# M1703C.net
KiCad netlist of a schematic drawn in EAGLE
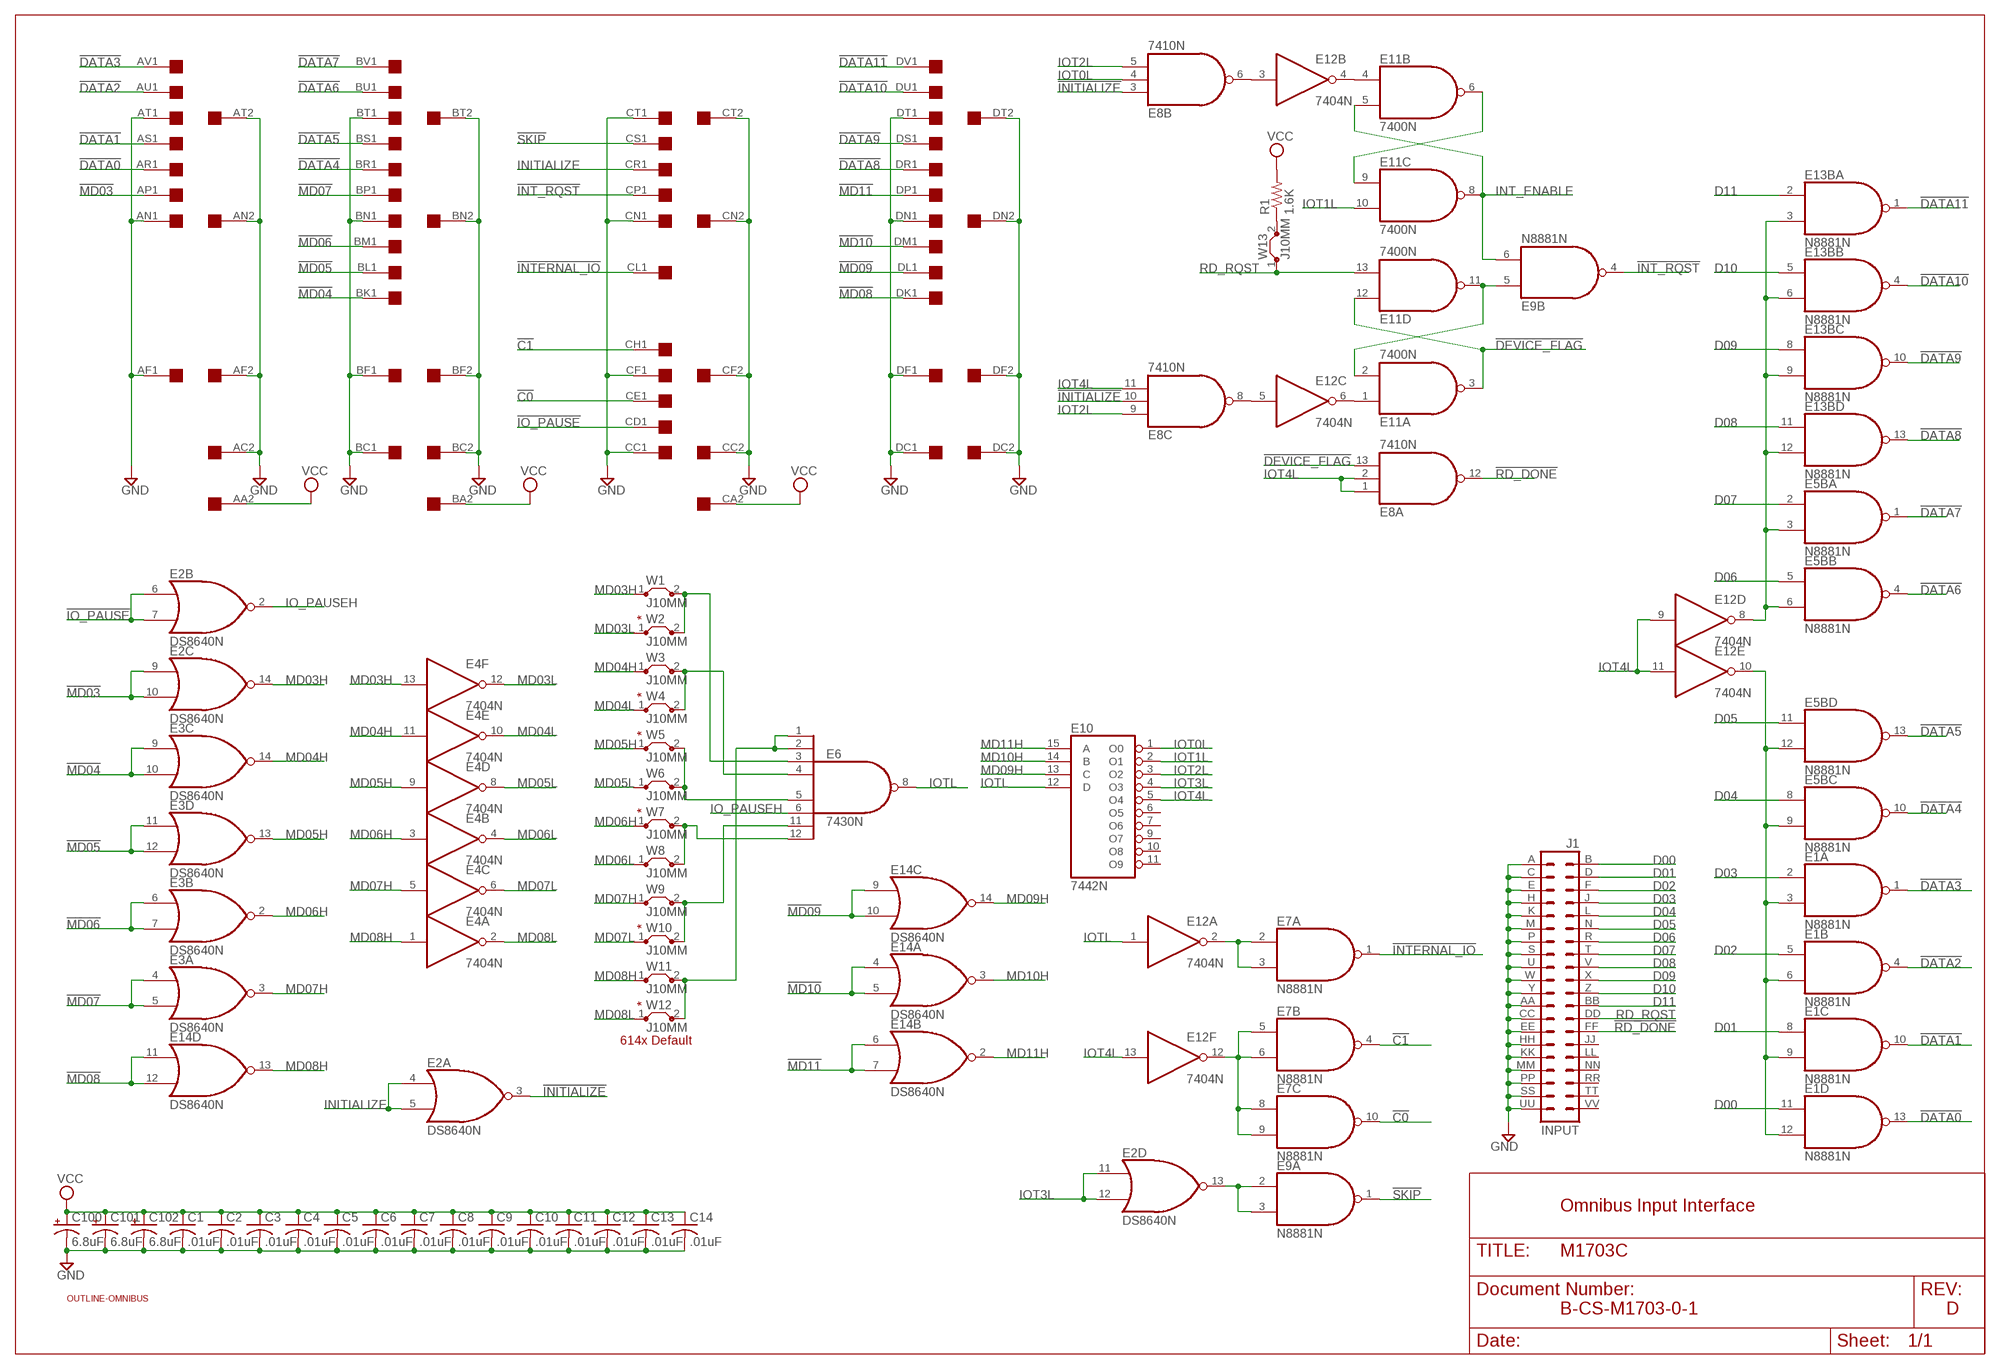
[diagram p0: schematic, sheet 1]

(export (version "E")
  (design (tool "Eeschema 10.0.6"))
  (components
    (comp (ref "C1")
      (value ".01uF")
      (footprint "eagle-import:C075-032X103")
      (libsource (lib "eagle-import") (part "C-US075-032X103"))
    )
    (comp (ref "C2")
      (value ".01uF")
      (footprint "eagle-import:C075-032X103")
      (libsource (lib "eagle-import") (part "C-US075-032X103"))
    )
    (comp (ref "C3")
      (value ".01uF")
      (footprint "eagle-import:C075-032X103")
      (libsource (lib "eagle-import") (part "C-US075-032X103"))
    )
    (comp (ref "C4")
      (value ".01uF")
      (footprint "eagle-import:C075-032X103")
      (libsource (lib "eagle-import") (part "C-US075-032X103"))
    )
    (comp (ref "C5")
      (value ".01uF")
      (footprint "eagle-import:C075-032X103")
      (libsource (lib "eagle-import") (part "C-US075-032X103"))
    )
    (comp (ref "C6")
      (value ".01uF")
      (footprint "eagle-import:C075-032X103")
      (libsource (lib "eagle-import") (part "C-US075-032X103"))
    )
    (comp (ref "C7")
      (value ".01uF")
      (footprint "eagle-import:C075-032X103")
      (libsource (lib "eagle-import") (part "C-US075-032X103"))
    )
    (comp (ref "C8")
      (value ".01uF")
      (footprint "eagle-import:C075-032X103")
      (libsource (lib "eagle-import") (part "C-US075-032X103"))
    )
    (comp (ref "C9")
      (value ".01uF")
      (footprint "eagle-import:C075-032X103")
      (libsource (lib "eagle-import") (part "C-US075-032X103"))
    )
    (comp (ref "C10")
      (value ".01uF")
      (footprint "eagle-import:C075-032X103")
      (libsource (lib "eagle-import") (part "C-US075-032X103"))
    )
    (comp (ref "C11")
      (value ".01uF")
      (footprint "eagle-import:C075-032X103")
      (libsource (lib "eagle-import") (part "C-US075-032X103"))
    )
    (comp (ref "C12")
      (value ".01uF")
      (footprint "eagle-import:C075-032X103")
      (libsource (lib "eagle-import") (part "C-US075-032X103"))
    )
    (comp (ref "C13")
      (value ".01uF")
      (footprint "eagle-import:C075-032X103")
      (libsource (lib "eagle-import") (part "C-US075-032X103"))
    )
    (comp (ref "C14")
      (value ".01uF")
      (footprint "eagle-import:C075-032X103")
      (libsource (lib "eagle-import") (part "C-US075-032X103"))
    )
    (comp (ref "C100")
      (value "6.8uF")
      (footprint "eagle-import:E12-8")
      (libsource (lib "eagle-import") (part "CPOL-USE20-8AXIAL"))
    )
    (comp (ref "C101")
      (value "6.8uF")
      (footprint "eagle-import:E12-8")
      (libsource (lib "eagle-import") (part "CPOL-USE20-8AXIAL"))
    )
    (comp (ref "C102")
      (value "6.8uF")
      (footprint "eagle-import:E12-8")
      (libsource (lib "eagle-import") (part "CPOL-USE20-8AXIAL"))
    )
    (comp (ref "E1")
      (value "N8881N")
      (footprint "eagle-import:DIL14")
      (libsource (lib "eagle-import") (part "N8881N"))
    )
    (comp (ref "E2")
      (value "DS8640N")
      (footprint "eagle-import:DIL14")
      (libsource (lib "eagle-import") (part "DS8640N"))
    )
    (comp (ref "E3")
      (value "DS8640N")
      (footprint "eagle-import:DIL14")
      (libsource (lib "eagle-import") (part "DS8640N"))
    )
    (comp (ref "E4")
      (value "7404N")
      (footprint "eagle-import:DIL14")
      (libsource (lib "eagle-import") (part "7404N"))
    )
    (comp (ref "E5B")
      (value "N8881N")
      (footprint "eagle-import:DIL14")
      (libsource (lib "eagle-import") (part "N8881N"))
    )
    (comp (ref "E6")
      (value "7430N")
      (footprint "eagle-import:DIL14")
      (libsource (lib "eagle-import") (part "7430N"))
    )
    (comp (ref "E7")
      (value "N8881N")
      (footprint "eagle-import:DIL14")
      (libsource (lib "eagle-import") (part "N8881N"))
    )
    (comp (ref "E8")
      (value "7410N")
      (footprint "eagle-import:DIL14")
      (libsource (lib "eagle-import") (part "7410N"))
    )
    (comp (ref "E9")
      (value "N8881N")
      (footprint "eagle-import:DIL14")
      (libsource (lib "eagle-import") (part "N8881N"))
    )
    (comp (ref "E10")
      (value "7442N")
      (footprint "eagle-import:DIL16")
      (libsource (lib "eagle-import") (part "7442NLS"))
    )
    (comp (ref "E11")
      (value "7400N")
      (footprint "eagle-import:DIL14")
      (libsource (lib "eagle-import") (part "7400N"))
    )
    (comp (ref "E12")
      (value "7404N")
      (footprint "eagle-import:DIL14")
      (libsource (lib "eagle-import") (part "7404N"))
    )
    (comp (ref "E13B")
      (value "N8881N")
      (footprint "eagle-import:DIL14")
      (libsource (lib "eagle-import") (part "N8881N"))
    )
    (comp (ref "E14")
      (value "DS8640N")
      (footprint "eagle-import:DIL14")
      (libsource (lib "eagle-import") (part "DS8640N"))
    )
    (comp (ref "J1")
      (value "INPUT")
      (footprint "eagle-import:DEC40PINH")
      (libsource (lib "eagle-import") (part "DEC40PINH"))
    )
    (comp (ref "R1")
      (value "1.6K")
      (footprint "eagle-import:0207_10")
      (libsource (lib "eagle-import") (part "R-US_0207/10"))
    )
    (comp (ref "U$2")
      (value "QUAD")
      (footprint "eagle-import:EDGE-CON8")
      (libsource (lib "eagle-import") (part "QUAD"))
    )
    (comp (ref "U$4")
      (value "OUTLINE-OMNIBUS")
      (footprint "eagle-import:OMNIBUS")
      (libsource (lib "eagle-import") (part "OUTLINE-OMNIBUS"))
    )
    (comp (ref "W1")
      (value "J10MM")
      (footprint "eagle-import:10")
      (libsource (lib "eagle-import") (part "J10MM"))
    )
    (comp (ref "W2")
      (value "J10MM")
      (footprint "eagle-import:10")
      (libsource (lib "eagle-import") (part "J10MM"))
    )
    (comp (ref "W3")
      (value "J10MM")
      (footprint "eagle-import:10")
      (libsource (lib "eagle-import") (part "J10MM"))
    )
    (comp (ref "W4")
      (value "J10MM")
      (footprint "eagle-import:10")
      (libsource (lib "eagle-import") (part "J10MM"))
    )
    (comp (ref "W5")
      (value "J10MM")
      (footprint "eagle-import:10")
      (libsource (lib "eagle-import") (part "J10MM"))
    )
    (comp (ref "W6")
      (value "J10MM")
      (footprint "eagle-import:10")
      (libsource (lib "eagle-import") (part "J10MM"))
    )
    (comp (ref "W7")
      (value "J10MM")
      (footprint "eagle-import:10")
      (libsource (lib "eagle-import") (part "J10MM"))
    )
    (comp (ref "W8")
      (value "J10MM")
      (footprint "eagle-import:10")
      (libsource (lib "eagle-import") (part "J10MM"))
    )
    (comp (ref "W9")
      (value "J10MM")
      (footprint "eagle-import:10")
      (libsource (lib "eagle-import") (part "J10MM"))
    )
    (comp (ref "W10")
      (value "J10MM")
      (footprint "eagle-import:10")
      (libsource (lib "eagle-import") (part "J10MM"))
    )
    (comp (ref "W11")
      (value "J10MM")
      (footprint "eagle-import:10")
      (libsource (lib "eagle-import") (part "J10MM"))
    )
    (comp (ref "W12")
      (value "J10MM")
      (footprint "eagle-import:10")
      (libsource (lib "eagle-import") (part "J10MM"))
    )
    (comp (ref "W13")
      (value "J10MM")
      (footprint "eagle-import:10")
      (libsource (lib "eagle-import") (part "J10MM"))
    )
  )
  (nets
    (net (code "1") (name "/D00") (class "Default")
      (node (ref "E1") (pin "11") (pinfunction "I0_11") (pintype "input"))
      (node (ref "J1") (pin "B") (pinfunction "2_B") (pintype "bidirectional"))
    )
    (net (code "2") (name "/D01") (class "Default")
      (node (ref "E1") (pin "8") (pinfunction "I0_8") (pintype "input"))
      (node (ref "J1") (pin "D") (pinfunction "4_D") (pintype "bidirectional"))
    )
    (net (code "3") (name "/D02") (class "Default")
      (node (ref "E1") (pin "5") (pinfunction "I0_5") (pintype "input"))
      (node (ref "J1") (pin "F") (pinfunction "6_F") (pintype "bidirectional"))
    )
    (net (code "4") (name "/D03") (class "Default")
      (node (ref "E1") (pin "2") (pinfunction "I0_2") (pintype "input"))
      (node (ref "J1") (pin "J") (pinfunction "8_J") (pintype "bidirectional"))
    )
    (net (code "5") (name "/D04") (class "Default")
      (node (ref "E5B") (pin "8") (pinfunction "I0_8") (pintype "input"))
      (node (ref "J1") (pin "L") (pinfunction "10_L") (pintype "bidirectional"))
    )
    (net (code "6") (name "/D05") (class "Default")
      (node (ref "E5B") (pin "11") (pinfunction "I0_11") (pintype "input"))
      (node (ref "J1") (pin "N") (pinfunction "12_N") (pintype "bidirectional"))
    )
    (net (code "7") (name "/D06") (class "Default")
      (node (ref "E5B") (pin "5") (pinfunction "I0_5") (pintype "input"))
      (node (ref "J1") (pin "R") (pinfunction "14_R") (pintype "bidirectional"))
    )
    (net (code "8") (name "/D07") (class "Default")
      (node (ref "E5B") (pin "2") (pinfunction "I0_2") (pintype "input"))
      (node (ref "J1") (pin "T") (pinfunction "16_T") (pintype "bidirectional"))
    )
    (net (code "9") (name "/D08") (class "Default")
      (node (ref "E13B") (pin "11") (pinfunction "I0_11") (pintype "input"))
      (node (ref "J1") (pin "V") (pinfunction "18_V") (pintype "bidirectional"))
    )
    (net (code "10") (name "/D09") (class "Default")
      (node (ref "E13B") (pin "8") (pinfunction "I0_8") (pintype "input"))
      (node (ref "J1") (pin "X") (pinfunction "20_X") (pintype "bidirectional"))
    )
    (net (code "11") (name "/D10") (class "Default")
      (node (ref "E13B") (pin "5") (pinfunction "I0_5") (pintype "input"))
      (node (ref "J1") (pin "Z") (pinfunction "22_Z") (pintype "bidirectional"))
    )
    (net (code "12") (name "/D11") (class "Default")
      (node (ref "E13B") (pin "2") (pinfunction "I0_2") (pintype "input"))
      (node (ref "J1") (pin "BB") (pinfunction "24_BB") (pintype "bidirectional"))
    )
    (net (code "13") (name "/INITIALIZE") (class "Default")
      (node (ref "E2") (pin "4") (pinfunction "I0_4") (pintype "input"))
      (node (ref "E2") (pin "5") (pinfunction "I1_5") (pintype "input"))
      (node (ref "U$2") (pin "CR1") (pinfunction "1_CR1") (pintype "bidirectional"))
    )
    (net (code "14") (name "/INT_ENABLE") (class "Default")
      (node (ref "E11") (pin "5") (pinfunction "I1_5") (pintype "input"))
      (node (ref "E11") (pin "8") (pinfunction "O_8") (pintype "output"))
      (node (ref "E9") (pin "6") (pinfunction "I1_6") (pintype "input"))
    )
    (net (code "15") (name "/IOT0L") (class "Default")
      (node (ref "E10") (pin "1") (pinfunction "O0_1") (pintype "output"))
      (node (ref "E8") (pin "4") (pinfunction "I1_4") (pintype "input"))
    )
    (net (code "16") (name "/IOT1L") (class "Default")
      (node (ref "E10") (pin "2") (pinfunction "O1_2") (pintype "output"))
      (node (ref "E11") (pin "10") (pinfunction "I1_10") (pintype "input"))
    )
    (net (code "17") (name "/IOT2L") (class "Default")
      (node (ref "E10") (pin "3") (pinfunction "O2_3") (pintype "output"))
      (node (ref "E8") (pin "5") (pinfunction "I2_5") (pintype "input"))
      (node (ref "E8") (pin "9") (pinfunction "I0_9") (pintype "input"))
    )
    (net (code "18") (name "/IOT3L") (class "Default")
      (node (ref "E10") (pin "4") (pinfunction "O3_4") (pintype "output"))
      (node (ref "E2") (pin "11") (pinfunction "I0_11") (pintype "input"))
      (node (ref "E2") (pin "12") (pinfunction "I1_12") (pintype "input"))
    )
    (net (code "19") (name "/IOT4L") (class "Default")
      (node (ref "E10") (pin "5") (pinfunction "O4_5") (pintype "output"))
      (node (ref "E12") (pin "11") (pinfunction "I_11") (pintype "input"))
      (node (ref "E12") (pin "13") (pinfunction "I_13") (pintype "input"))
      (node (ref "E12") (pin "9") (pinfunction "I_9") (pintype "input"))
      (node (ref "E8") (pin "1") (pinfunction "I0_1") (pintype "input"))
      (node (ref "E8") (pin "11") (pinfunction "I2_11") (pintype "input"))
      (node (ref "E8") (pin "2") (pinfunction "I1_2") (pintype "input"))
    )
    (net (code "20") (name "/IOTL") (class "Default")
      (node (ref "E10") (pin "12") (pinfunction "D_12") (pintype "input"))
      (node (ref "E12") (pin "1") (pinfunction "I_1") (pintype "input"))
      (node (ref "E6") (pin "8") (pinfunction "O_8") (pintype "output"))
    )
    (net (code "21") (name "/IO_PAUSEH") (class "Default")
      (node (ref "E2") (pin "2") (pinfunction "O_2") (pintype "output"))
      (node (ref "E6") (pin "6") (pinfunction "I5_6") (pintype "input"))
    )
    (net (code "22") (name "/MD03H") (class "Default")
      (node (ref "E2") (pin "14") (pinfunction "O_14") (pintype "output"))
      (node (ref "E4") (pin "13") (pinfunction "I_13") (pintype "input"))
      (node (ref "W1") (pin "1") (pinfunction "1_1") (pintype "passive"))
    )
    (net (code "23") (name "/MD03L") (class "Default")
      (node (ref "E4") (pin "12") (pinfunction "O_12") (pintype "output"))
      (node (ref "W2") (pin "1") (pinfunction "1_1") (pintype "passive"))
    )
    (net (code "24") (name "/MD04H") (class "Default")
      (node (ref "E3") (pin "14") (pinfunction "O_14") (pintype "output"))
      (node (ref "E4") (pin "11") (pinfunction "I_11") (pintype "input"))
      (node (ref "W3") (pin "1") (pinfunction "1_1") (pintype "passive"))
    )
    (net (code "25") (name "/MD04L") (class "Default")
      (node (ref "E4") (pin "10") (pinfunction "O_10") (pintype "output"))
      (node (ref "W4") (pin "1") (pinfunction "1_1") (pintype "passive"))
    )
    (net (code "26") (name "/MD05H") (class "Default")
      (node (ref "E3") (pin "13") (pinfunction "O_13") (pintype "output"))
      (node (ref "E4") (pin "9") (pinfunction "I_9") (pintype "input"))
      (node (ref "W5") (pin "1") (pinfunction "1_1") (pintype "passive"))
    )
    (net (code "27") (name "/MD05L") (class "Default")
      (node (ref "E4") (pin "8") (pinfunction "O_8") (pintype "output"))
      (node (ref "W6") (pin "1") (pinfunction "1_1") (pintype "passive"))
    )
    (net (code "28") (name "/MD06H") (class "Default")
      (node (ref "E3") (pin "2") (pinfunction "O_2") (pintype "output"))
      (node (ref "E4") (pin "3") (pinfunction "I_3") (pintype "input"))
      (node (ref "W7") (pin "1") (pinfunction "1_1") (pintype "passive"))
    )
    (net (code "29") (name "/MD06L") (class "Default")
      (node (ref "E4") (pin "4") (pinfunction "O_4") (pintype "output"))
      (node (ref "W8") (pin "1") (pinfunction "1_1") (pintype "passive"))
    )
    (net (code "30") (name "/MD07H") (class "Default")
      (node (ref "E3") (pin "3") (pinfunction "O_3") (pintype "output"))
      (node (ref "E4") (pin "5") (pinfunction "I_5") (pintype "input"))
      (node (ref "W9") (pin "1") (pinfunction "1_1") (pintype "passive"))
    )
    (net (code "31") (name "/MD07L") (class "Default")
      (node (ref "E4") (pin "6") (pinfunction "O_6") (pintype "output"))
      (node (ref "W10") (pin "1") (pinfunction "1_1") (pintype "passive"))
    )
    (net (code "32") (name "/MD08H") (class "Default")
      (node (ref "E14") (pin "13") (pinfunction "O_13") (pintype "output"))
      (node (ref "E4") (pin "1") (pinfunction "I_1") (pintype "input"))
      (node (ref "W11") (pin "1") (pinfunction "1_1") (pintype "passive"))
    )
    (net (code "33") (name "/MD08L") (class "Default")
      (node (ref "E4") (pin "2") (pinfunction "O_2") (pintype "output"))
      (node (ref "W12") (pin "1") (pinfunction "1_1") (pintype "passive"))
    )
    (net (code "34") (name "/MD09H") (class "Default")
      (node (ref "E10") (pin "13") (pinfunction "C_13") (pintype "input"))
      (node (ref "E14") (pin "14") (pinfunction "O_14") (pintype "output"))
    )
    (net (code "35") (name "/MD10H") (class "Default")
      (node (ref "E10") (pin "14") (pinfunction "B_14") (pintype "input"))
      (node (ref "E14") (pin "3") (pinfunction "O_3") (pintype "output"))
    )
    (net (code "36") (name "/MD11H") (class "Default")
      (node (ref "E10") (pin "15") (pinfunction "A_15") (pintype "input"))
      (node (ref "E14") (pin "2") (pinfunction "O_2") (pintype "output"))
    )
    (net (code "37") (name "/RD_RQST") (class "Default")
      (node (ref "E11") (pin "13") (pinfunction "I1_13") (pintype "input"))
      (node (ref "J1") (pin "DD") (pinfunction "26_DD") (pintype "bidirectional"))
      (node (ref "W13") (pin "1") (pinfunction "1_1") (pintype "passive"))
    )
    (net (code "38") (name "/~{C0}") (class "Default")
      (node (ref "E7") (pin "10") (pinfunction "O_10") (pintype "open_collector"))
      (node (ref "U$2") (pin "CE1") (pinfunction "1_CE1") (pintype "bidirectional"))
    )
    (net (code "39") (name "/~{C1}") (class "Default")
      (node (ref "E7") (pin "4") (pinfunction "O_4") (pintype "open_collector"))
      (node (ref "U$2") (pin "CH1") (pinfunction "1_CH1") (pintype "bidirectional"))
    )
    (net (code "40") (name "/~{DATA0}") (class "Default")
      (node (ref "E1") (pin "13") (pinfunction "O_13") (pintype "open_collector"))
      (node (ref "U$2") (pin "AR1") (pinfunction "1_AR1") (pintype "bidirectional"))
    )
    (net (code "41") (name "/~{DATA1}") (class "Default")
      (node (ref "E1") (pin "10") (pinfunction "O_10") (pintype "open_collector"))
      (node (ref "U$2") (pin "AS1") (pinfunction "1_AS1") (pintype "bidirectional"))
    )
    (net (code "42") (name "/~{DATA2}") (class "Default")
      (node (ref "E1") (pin "4") (pinfunction "O_4") (pintype "open_collector"))
      (node (ref "U$2") (pin "AU1") (pinfunction "1_AU1") (pintype "bidirectional"))
    )
    (net (code "43") (name "/~{DATA3}") (class "Default")
      (node (ref "E1") (pin "1") (pinfunction "O_1") (pintype "open_collector"))
      (node (ref "U$2") (pin "AV1") (pinfunction "1_AV1") (pintype "bidirectional"))
    )
    (net (code "44") (name "/~{DATA4}") (class "Default")
      (node (ref "E5B") (pin "10") (pinfunction "O_10") (pintype "open_collector"))
      (node (ref "U$2") (pin "BR1") (pinfunction "1_BR1") (pintype "bidirectional"))
    )
    (net (code "45") (name "/~{DATA5}") (class "Default")
      (node (ref "E5B") (pin "13") (pinfunction "O_13") (pintype "open_collector"))
      (node (ref "U$2") (pin "BS1") (pinfunction "1_BS1") (pintype "bidirectional"))
    )
    (net (code "46") (name "/~{DATA6}") (class "Default")
      (node (ref "E5B") (pin "4") (pinfunction "O_4") (pintype "open_collector"))
      (node (ref "U$2") (pin "BU1") (pinfunction "1_BU1") (pintype "bidirectional"))
    )
    (net (code "47") (name "/~{DATA7}") (class "Default")
      (node (ref "E5B") (pin "1") (pinfunction "O_1") (pintype "open_collector"))
      (node (ref "U$2") (pin "BV1") (pinfunction "1_BV1") (pintype "bidirectional"))
    )
    (net (code "48") (name "/~{DATA8}") (class "Default")
      (node (ref "E13B") (pin "13") (pinfunction "O_13") (pintype "open_collector"))
      (node (ref "U$2") (pin "DR1") (pinfunction "1_DR1") (pintype "bidirectional"))
    )
    (net (code "49") (name "/~{DATA9}") (class "Default")
      (node (ref "E13B") (pin "10") (pinfunction "O_10") (pintype "open_collector"))
      (node (ref "U$2") (pin "DS1") (pinfunction "1_DS1") (pintype "bidirectional"))
    )
    (net (code "50") (name "/~{DATA10}") (class "Default")
      (node (ref "E13B") (pin "4") (pinfunction "O_4") (pintype "open_collector"))
      (node (ref "U$2") (pin "DU1") (pinfunction "1_DU1") (pintype "bidirectional"))
    )
    (net (code "51") (name "/~{DATA11}") (class "Default")
      (node (ref "E13B") (pin "1") (pinfunction "O_1") (pintype "open_collector"))
      (node (ref "U$2") (pin "DV1") (pinfunction "1_DV1") (pintype "bidirectional"))
    )
    (net (code "52") (name "/~{DEVICE_FLAG}") (class "Default")
      (node (ref "E11") (pin "12") (pinfunction "I0_12") (pintype "input"))
      (node (ref "E11") (pin "3") (pinfunction "O_3") (pintype "output"))
      (node (ref "E8") (pin "13") (pinfunction "I2_13") (pintype "input"))
    )
    (net (code "53") (name "/~{INITIALIZE}") (class "Default")
      (node (ref "E2") (pin "3") (pinfunction "O_3") (pintype "output"))
      (node (ref "E8") (pin "10") (pinfunction "I1_10") (pintype "input"))
      (node (ref "E8") (pin "3") (pinfunction "I0_3") (pintype "input"))
    )
    (net (code "54") (name "/~{INTERNAL_IO}") (class "Default")
      (node (ref "E7") (pin "1") (pinfunction "O_1") (pintype "open_collector"))
      (node (ref "U$2") (pin "CL1") (pinfunction "1_CL1") (pintype "bidirectional"))
    )
    (net (code "55") (name "/~{INT_RQST}") (class "Default")
      (node (ref "E9") (pin "4") (pinfunction "O_4") (pintype "open_collector"))
      (node (ref "U$2") (pin "CP1") (pinfunction "1_CP1") (pintype "bidirectional"))
    )
    (net (code "56") (name "/~{IO_PAUSE}") (class "Default")
      (node (ref "E2") (pin "6") (pinfunction "I0_6") (pintype "input"))
      (node (ref "E2") (pin "7") (pinfunction "I1_7") (pintype "input"))
      (node (ref "U$2") (pin "CD1") (pinfunction "1_CD1") (pintype "bidirectional"))
    )
    (net (code "57") (name "/~{MD03}") (class "Default")
      (node (ref "E2") (pin "10") (pinfunction "I1_10") (pintype "input"))
      (node (ref "E2") (pin "9") (pinfunction "I0_9") (pintype "input"))
      (node (ref "U$2") (pin "AP1") (pinfunction "1_AP1") (pintype "bidirectional"))
    )
    (net (code "58") (name "/~{MD04}") (class "Default")
      (node (ref "E3") (pin "10") (pinfunction "I1_10") (pintype "input"))
      (node (ref "E3") (pin "9") (pinfunction "I0_9") (pintype "input"))
      (node (ref "U$2") (pin "BK1") (pinfunction "1_BK1") (pintype "bidirectional"))
    )
    (net (code "59") (name "/~{MD05}") (class "Default")
      (node (ref "E3") (pin "11") (pinfunction "I0_11") (pintype "input"))
      (node (ref "E3") (pin "12") (pinfunction "I1_12") (pintype "input"))
      (node (ref "U$2") (pin "BL1") (pinfunction "1_BL1") (pintype "bidirectional"))
    )
    (net (code "60") (name "/~{MD06}") (class "Default")
      (node (ref "E3") (pin "6") (pinfunction "I0_6") (pintype "input"))
      (node (ref "E3") (pin "7") (pinfunction "I1_7") (pintype "input"))
      (node (ref "U$2") (pin "BM1") (pinfunction "1_BM1") (pintype "bidirectional"))
    )
    (net (code "61") (name "/~{MD07}") (class "Default")
      (node (ref "E3") (pin "4") (pinfunction "I0_4") (pintype "input"))
      (node (ref "E3") (pin "5") (pinfunction "I1_5") (pintype "input"))
      (node (ref "U$2") (pin "BP1") (pinfunction "1_BP1") (pintype "bidirectional"))
    )
    (net (code "62") (name "/~{MD08}") (class "Default")
      (node (ref "E14") (pin "11") (pinfunction "I0_11") (pintype "input"))
      (node (ref "E14") (pin "12") (pinfunction "I1_12") (pintype "input"))
      (node (ref "U$2") (pin "DK1") (pinfunction "1_DK1") (pintype "bidirectional"))
    )
    (net (code "63") (name "/~{MD09}") (class "Default")
      (node (ref "E14") (pin "10") (pinfunction "I1_10") (pintype "input"))
      (node (ref "E14") (pin "9") (pinfunction "I0_9") (pintype "input"))
      (node (ref "U$2") (pin "DL1") (pinfunction "1_DL1") (pintype "bidirectional"))
    )
    (net (code "64") (name "/~{MD10}") (class "Default")
      (node (ref "E14") (pin "4") (pinfunction "I0_4") (pintype "input"))
      (node (ref "E14") (pin "5") (pinfunction "I1_5") (pintype "input"))
      (node (ref "U$2") (pin "DM1") (pinfunction "1_DM1") (pintype "bidirectional"))
    )
    (net (code "65") (name "/~{MD11}") (class "Default")
      (node (ref "E14") (pin "6") (pinfunction "I0_6") (pintype "input"))
      (node (ref "E14") (pin "7") (pinfunction "I1_7") (pintype "input"))
      (node (ref "U$2") (pin "DP1") (pinfunction "1_DP1") (pintype "bidirectional"))
    )
    (net (code "66") (name "/~{RD_DONE}") (class "Default")
      (node (ref "E8") (pin "12") (pinfunction "O_12") (pintype "output"))
      (node (ref "J1") (pin "FF") (pinfunction "28_FF") (pintype "bidirectional"))
    )
    (net (code "67") (name "/~{SKIP}") (class "Default")
      (node (ref "E9") (pin "1") (pinfunction "O_1") (pintype "open_collector"))
      (node (ref "U$2") (pin "CS1") (pinfunction "1_CS1") (pintype "bidirectional"))
    )
    (net (code "68") (name "GND") (class "Default")
      (node (ref "C1") (pin "2") (pinfunction "2_2") (pintype "passive"))
      (node (ref "C10") (pin "2") (pinfunction "2_2") (pintype "passive"))
      (node (ref "C100") (pin "-") (pinfunction "-_-") (pintype "passive"))
      (node (ref "C101") (pin "-") (pinfunction "-_-") (pintype "passive"))
      (node (ref "C102") (pin "-") (pinfunction "-_-") (pintype "passive"))
      (node (ref "C11") (pin "2") (pinfunction "2_2") (pintype "passive"))
      (node (ref "C12") (pin "2") (pinfunction "2_2") (pintype "passive"))
      (node (ref "C13") (pin "2") (pinfunction "2_2") (pintype "passive"))
      (node (ref "C14") (pin "2") (pinfunction "2_2") (pintype "passive"))
      (node (ref "C2") (pin "2") (pinfunction "2_2") (pintype "passive"))
      (node (ref "C3") (pin "2") (pinfunction "2_2") (pintype "passive"))
      (node (ref "C4") (pin "2") (pinfunction "2_2") (pintype "passive"))
      (node (ref "C5") (pin "2") (pinfunction "2_2") (pintype "passive"))
      (node (ref "C6") (pin "2") (pinfunction "2_2") (pintype "passive"))
      (node (ref "C7") (pin "2") (pinfunction "2_2") (pintype "passive"))
      (node (ref "C8") (pin "2") (pinfunction "2_2") (pintype "passive"))
      (node (ref "C9") (pin "2") (pinfunction "2_2") (pintype "passive"))
      (node (ref "J1") (pin "A") (pinfunction "1_A") (pintype "bidirectional"))
      (node (ref "J1") (pin "AA") (pinfunction "23_AA") (pintype "bidirectional"))
      (node (ref "J1") (pin "C") (pinfunction "3_C") (pintype "bidirectional"))
      (node (ref "J1") (pin "CC") (pinfunction "25_CC") (pintype "bidirectional"))
      (node (ref "J1") (pin "E") (pinfunction "5_E") (pintype "bidirectional"))
      (node (ref "J1") (pin "EE") (pinfunction "27_EE") (pintype "bidirectional"))
      (node (ref "J1") (pin "H") (pinfunction "7_H") (pintype "bidirectional"))
      (node (ref "J1") (pin "HH") (pinfunction "29_HH") (pintype "bidirectional"))
      (node (ref "J1") (pin "K") (pinfunction "9_K") (pintype "bidirectional"))
      (node (ref "J1") (pin "KK") (pinfunction "31_KK") (pintype "bidirectional"))
      (node (ref "J1") (pin "M") (pinfunction "11_M") (pintype "bidirectional"))
      (node (ref "J1") (pin "MM") (pinfunction "33_MM") (pintype "bidirectional"))
      (node (ref "J1") (pin "P") (pinfunction "13_P") (pintype "bidirectional"))
      (node (ref "J1") (pin "PP") (pinfunction "35_PP") (pintype "bidirectional"))
      (node (ref "J1") (pin "S") (pinfunction "15_S") (pintype "bidirectional"))
      (node (ref "J1") (pin "SS") (pinfunction "37_SS") (pintype "bidirectional"))
      (node (ref "J1") (pin "U") (pinfunction "17_U") (pintype "bidirectional"))
      (node (ref "J1") (pin "UU") (pinfunction "39_UU") (pintype "bidirectional"))
      (node (ref "J1") (pin "W") (pinfunction "19_W") (pintype "bidirectional"))
      (node (ref "J1") (pin "Y") (pinfunction "21_Y") (pintype "bidirectional"))
      (node (ref "U$2") (pin "AC2") (pinfunction "1_AC2") (pintype "bidirectional"))
      (node (ref "U$2") (pin "AF1") (pinfunction "1_AF1") (pintype "bidirectional"))
      (node (ref "U$2") (pin "AF2") (pinfunction "1_AF2") (pintype "bidirectional"))
      (node (ref "U$2") (pin "AN1") (pinfunction "1_AN1") (pintype "bidirectional"))
      (node (ref "U$2") (pin "AN2") (pinfunction "1_AN2") (pintype "bidirectional"))
      (node (ref "U$2") (pin "AT1") (pinfunction "1_AT1") (pintype "bidirectional"))
      (node (ref "U$2") (pin "AT2") (pinfunction "1_AT2") (pintype "bidirectional"))
      (node (ref "U$2") (pin "BC1") (pinfunction "1_BC1") (pintype "bidirectional"))
      (node (ref "U$2") (pin "BC2") (pinfunction "1_BC2") (pintype "bidirectional"))
      (node (ref "U$2") (pin "BF1") (pinfunction "1_BF1") (pintype "bidirectional"))
      (node (ref "U$2") (pin "BF2") (pinfunction "1_BF2") (pintype "bidirectional"))
      (node (ref "U$2") (pin "BN1") (pinfunction "1_BN1") (pintype "bidirectional"))
      (node (ref "U$2") (pin "BN2") (pinfunction "1_BN2") (pintype "bidirectional"))
      (node (ref "U$2") (pin "BT1") (pinfunction "1_BT1") (pintype "bidirectional"))
      (node (ref "U$2") (pin "BT2") (pinfunction "1_BT2") (pintype "bidirectional"))
      (node (ref "U$2") (pin "CC1") (pinfunction "1_CC1") (pintype "bidirectional"))
      (node (ref "U$2") (pin "CC2") (pinfunction "1_CC2") (pintype "bidirectional"))
      (node (ref "U$2") (pin "CF1") (pinfunction "1_CF1") (pintype "bidirectional"))
      (node (ref "U$2") (pin "CF2") (pinfunction "1_CF2") (pintype "bidirectional"))
      (node (ref "U$2") (pin "CN1") (pinfunction "1_CN1") (pintype "bidirectional"))
      (node (ref "U$2") (pin "CN2") (pinfunction "1_CN2") (pintype "bidirectional"))
      (node (ref "U$2") (pin "CT1") (pinfunction "1_CT1") (pintype "bidirectional"))
      (node (ref "U$2") (pin "CT2") (pinfunction "1_CT2") (pintype "bidirectional"))
      (node (ref "U$2") (pin "DC1") (pinfunction "1_DC1") (pintype "bidirectional"))
      (node (ref "U$2") (pin "DC2") (pinfunction "1_DC2") (pintype "bidirectional"))
      (node (ref "U$2") (pin "DF1") (pinfunction "1_DF1") (pintype "bidirectional"))
      (node (ref "U$2") (pin "DF2") (pinfunction "1_DF2") (pintype "bidirectional"))
      (node (ref "U$2") (pin "DN1") (pinfunction "1_DN1") (pintype "bidirectional"))
      (node (ref "U$2") (pin "DN2") (pinfunction "1_DN2") (pintype "bidirectional"))
      (node (ref "U$2") (pin "DT1") (pinfunction "1_DT1") (pintype "bidirectional"))
      (node (ref "U$2") (pin "DT2") (pinfunction "1_DT2") (pintype "bidirectional"))
    )
    (net (code "69") (name "Net-(E2D-O)") (class "Default")
      (node (ref "E2") (pin "13") (pinfunction "O_13") (pintype "output"))
      (node (ref "E9") (pin "2") (pinfunction "I0_2") (pintype "input"))
      (node (ref "E9") (pin "3") (pinfunction "I1_3") (pintype "input"))
    )
    (net (code "70") (name "Net-(E6A-I0)") (class "Default")
      (node (ref "E6") (pin "1") (pinfunction "I0_1") (pintype "input"))
      (node (ref "E6") (pin "2") (pinfunction "I1_2") (pintype "input"))
      (node (ref "W11") (pin "2") (pinfunction "2_2") (pintype "passive"))
      (node (ref "W12") (pin "2") (pinfunction "2_2") (pintype "passive"))
    )
    (net (code "71") (name "Net-(E6A-I2)") (class "Default")
      (node (ref "E6") (pin "3") (pinfunction "I2_3") (pintype "input"))
      (node (ref "W1") (pin "2") (pinfunction "2_2") (pintype "passive"))
      (node (ref "W2") (pin "2") (pinfunction "2_2") (pintype "passive"))
    )
    (net (code "72") (name "Net-(E6A-I3)") (class "Default")
      (node (ref "E6") (pin "4") (pinfunction "I3_4") (pintype "input"))
      (node (ref "W3") (pin "2") (pinfunction "2_2") (pintype "passive"))
      (node (ref "W4") (pin "2") (pinfunction "2_2") (pintype "passive"))
    )
    (net (code "73") (name "Net-(E6A-I4)") (class "Default")
      (node (ref "E6") (pin "5") (pinfunction "I4_5") (pintype "input"))
      (node (ref "W5") (pin "2") (pinfunction "2_2") (pintype "passive"))
      (node (ref "W6") (pin "2") (pinfunction "2_2") (pintype "passive"))
    )
    (net (code "74") (name "Net-(E6A-I6)") (class "Default")
      (node (ref "E6") (pin "11") (pinfunction "I6_11") (pintype "input"))
      (node (ref "W10") (pin "2") (pinfunction "2_2") (pintype "passive"))
      (node (ref "W9") (pin "2") (pinfunction "2_2") (pintype "passive"))
    )
    (net (code "75") (name "Net-(E6A-I7)") (class "Default")
      (node (ref "E6") (pin "12") (pinfunction "I7_12") (pintype "input"))
      (node (ref "W7") (pin "2") (pinfunction "2_2") (pintype "passive"))
      (node (ref "W8") (pin "2") (pinfunction "2_2") (pintype "passive"))
    )
    (net (code "76") (name "Net-(E11A-I0)") (class "Default")
      (node (ref "E11") (pin "1") (pinfunction "I0_1") (pintype "input"))
      (node (ref "E12") (pin "6") (pinfunction "O_6") (pintype "output"))
    )
    (net (code "77") (name "Net-(E11A-I1)") (class "Default")
      (node (ref "E11") (pin "11") (pinfunction "O_11") (pintype "output"))
      (node (ref "E11") (pin "2") (pinfunction "I1_2") (pintype "input"))
      (node (ref "E9") (pin "5") (pinfunction "I0_5") (pintype "input"))
    )
    (net (code "78") (name "Net-(E11B-I0)") (class "Default")
      (node (ref "E11") (pin "4") (pinfunction "I0_4") (pintype "input"))
      (node (ref "E12") (pin "4") (pinfunction "O_4") (pintype "output"))
    )
    (net (code "79") (name "Net-(E11B-O)") (class "Default")
      (node (ref "E11") (pin "6") (pinfunction "O_6") (pintype "output"))
      (node (ref "E11") (pin "9") (pinfunction "I0_9") (pintype "input"))
    )
    (net (code "80") (name "Net-(E12A-O)") (class "Default")
      (node (ref "E12") (pin "2") (pinfunction "O_2") (pintype "output"))
      (node (ref "E7") (pin "2") (pinfunction "I0_2") (pintype "input"))
      (node (ref "E7") (pin "3") (pinfunction "I1_3") (pintype "input"))
    )
    (net (code "81") (name "Net-(E12B-I)") (class "Default")
      (node (ref "E12") (pin "3") (pinfunction "I_3") (pintype "input"))
      (node (ref "E8") (pin "6") (pinfunction "O_6") (pintype "output"))
    )
    (net (code "82") (name "Net-(E12C-I)") (class "Default")
      (node (ref "E12") (pin "5") (pinfunction "I_5") (pintype "input"))
      (node (ref "E8") (pin "8") (pinfunction "O_8") (pintype "output"))
    )
    (net (code "83") (name "Net-(E12D-O)") (class "Default")
      (node (ref "E12") (pin "8") (pinfunction "O_8") (pintype "output"))
      (node (ref "E13B") (pin "12") (pinfunction "I1_12") (pintype "input"))
      (node (ref "E13B") (pin "3") (pinfunction "I1_3") (pintype "input"))
      (node (ref "E13B") (pin "6") (pinfunction "I1_6") (pintype "input"))
      (node (ref "E13B") (pin "9") (pinfunction "I1_9") (pintype "input"))
      (node (ref "E5B") (pin "3") (pinfunction "I1_3") (pintype "input"))
      (node (ref "E5B") (pin "6") (pinfunction "I1_6") (pintype "input"))
    )
    (net (code "84") (name "Net-(E12E-O)") (class "Default")
      (node (ref "E1") (pin "12") (pinfunction "I1_12") (pintype "input"))
      (node (ref "E1") (pin "3") (pinfunction "I1_3") (pintype "input"))
      (node (ref "E1") (pin "6") (pinfunction "I1_6") (pintype "input"))
      (node (ref "E1") (pin "9") (pinfunction "I1_9") (pintype "input"))
      (node (ref "E12") (pin "10") (pinfunction "O_10") (pintype "output"))
      (node (ref "E5B") (pin "12") (pinfunction "I1_12") (pintype "input"))
      (node (ref "E5B") (pin "9") (pinfunction "I1_9") (pintype "input"))
    )
    (net (code "85") (name "Net-(E12F-O)") (class "Default")
      (node (ref "E12") (pin "12") (pinfunction "O_12") (pintype "output"))
      (node (ref "E7") (pin "5") (pinfunction "I0_5") (pintype "input"))
      (node (ref "E7") (pin "6") (pinfunction "I1_6") (pintype "input"))
      (node (ref "E7") (pin "8") (pinfunction "I0_8") (pintype "input"))
      (node (ref "E7") (pin "9") (pinfunction "I1_9") (pintype "input"))
    )
    (net (code "86") (name "Net-(R1-Pad1)") (class "Default")
      (node (ref "R1") (pin "1") (pinfunction "1_1") (pintype "passive"))
      (node (ref "W13") (pin "2") (pinfunction "2_2") (pintype "passive"))
    )
    (net (code "87") (name "VCC") (class "Default")
      (node (ref "C1") (pin "1") (pinfunction "1_1") (pintype "passive"))
      (node (ref "C10") (pin "1") (pinfunction "1_1") (pintype "passive"))
      (node (ref "C100") (pin "+") (pinfunction "+_+") (pintype "passive"))
      (node (ref "C101") (pin "+") (pinfunction "+_+") (pintype "passive"))
      (node (ref "C102") (pin "+") (pinfunction "+_+") (pintype "passive"))
      (node (ref "C11") (pin "1") (pinfunction "1_1") (pintype "passive"))
      (node (ref "C12") (pin "1") (pinfunction "1_1") (pintype "passive"))
      (node (ref "C13") (pin "1") (pinfunction "1_1") (pintype "passive"))
      (node (ref "C14") (pin "1") (pinfunction "1_1") (pintype "passive"))
      (node (ref "C2") (pin "1") (pinfunction "1_1") (pintype "passive"))
      (node (ref "C3") (pin "1") (pinfunction "1_1") (pintype "passive"))
      (node (ref "C4") (pin "1") (pinfunction "1_1") (pintype "passive"))
      (node (ref "C5") (pin "1") (pinfunction "1_1") (pintype "passive"))
      (node (ref "C6") (pin "1") (pinfunction "1_1") (pintype "passive"))
      (node (ref "C7") (pin "1") (pinfunction "1_1") (pintype "passive"))
      (node (ref "C8") (pin "1") (pinfunction "1_1") (pintype "passive"))
      (node (ref "C9") (pin "1") (pinfunction "1_1") (pintype "passive"))
      (node (ref "R1") (pin "2") (pinfunction "2_2") (pintype "passive"))
      (node (ref "U$2") (pin "AA2") (pinfunction "1_AA2") (pintype "bidirectional"))
      (node (ref "U$2") (pin "BA2") (pinfunction "1_BA2") (pintype "bidirectional"))
      (node (ref "U$2") (pin "CA2") (pinfunction "1_CA2") (pintype "bidirectional"))
    )
    (net (code "88") (name "unconnected-(E10A-O5-Pad6)") (class "Default")
      (node (ref "E10") (pin "6") (pinfunction "O5_6") (pintype "output"))
    )
    (net (code "89") (name "unconnected-(E10A-O6-Pad7)") (class "Default")
      (node (ref "E10") (pin "7") (pinfunction "O6_7") (pintype "output"))
    )
    (net (code "90") (name "unconnected-(E10A-O7-Pad9)") (class "Default")
      (node (ref "E10") (pin "9") (pinfunction "O7_9") (pintype "output"))
    )
    (net (code "91") (name "unconnected-(E10A-O8-Pad10)") (class "Default")
      (node (ref "E10") (pin "10") (pinfunction "O8_10") (pintype "output"))
    )
    (net (code "92") (name "unconnected-(E10A-O9-Pad11)") (class "Default")
      (node (ref "E10") (pin "11") (pinfunction "O9_11") (pintype "output"))
    )
    (net (code "93") (name "unconnected-(J1-30-PadJJ)") (class "Default")
      (node (ref "J1") (pin "JJ") (pinfunction "30_JJ") (pintype "bidirectional"))
    )
    (net (code "94") (name "unconnected-(J1-32-PadLL)") (class "Default")
      (node (ref "J1") (pin "LL") (pinfunction "32_LL") (pintype "bidirectional"))
    )
    (net (code "95") (name "unconnected-(J1-34-PadNN)") (class "Default")
      (node (ref "J1") (pin "NN") (pinfunction "34_NN") (pintype "bidirectional"))
    )
    (net (code "96") (name "unconnected-(J1-36-PadRR)") (class "Default")
      (node (ref "J1") (pin "RR") (pinfunction "36_RR") (pintype "bidirectional"))
    )
    (net (code "97") (name "unconnected-(J1-38-PadTT)") (class "Default")
      (node (ref "J1") (pin "TT") (pinfunction "38_TT") (pintype "bidirectional"))
    )
    (net (code "98") (name "unconnected-(J1-40-PadVV)") (class "Default")
      (node (ref "J1") (pin "VV") (pinfunction "40_VV") (pintype "bidirectional"))
    )
  )
)
